# sound_localizer_v1.net
KiCad netlist of a schematic drawn in EAGLE
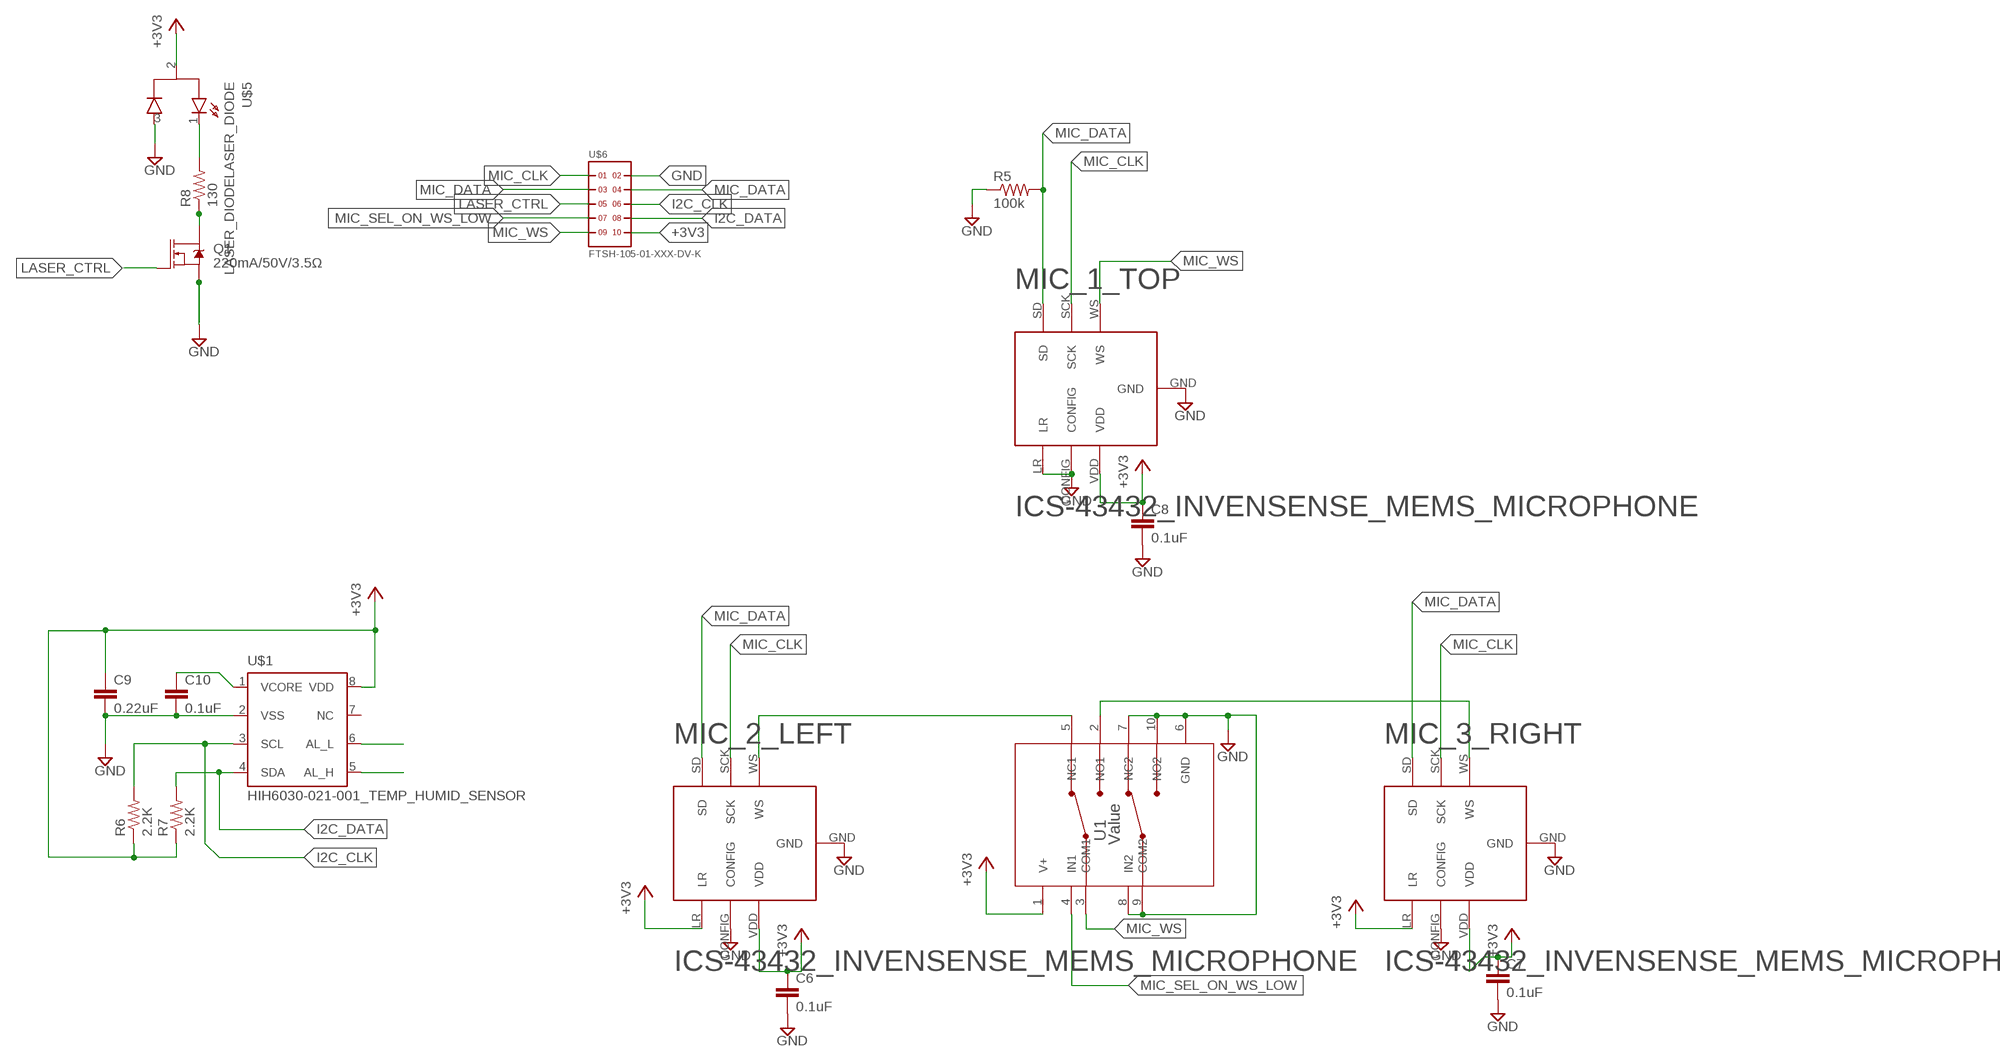
[diagram p0: schematic, sheet 1]

(export (version "E")
  (design (tool "Eeschema 10.0.6"))
  (components
    (comp (ref "C6")
      (value "0.1uF")
      (footprint "eagle-import:C0805K")
      (libsource (lib "eagle-import") (part "C-EUC0805K"))
    )
    (comp (ref "C7")
      (value "0.1uF")
      (footprint "eagle-import:C0805K")
      (libsource (lib "eagle-import") (part "C-EUC0805K"))
    )
    (comp (ref "C8")
      (value "0.1uF")
      (footprint "eagle-import:C0805K")
      (libsource (lib "eagle-import") (part "C-EUC0805K"))
    )
    (comp (ref "C9")
      (value "0.22uF")
      (footprint "eagle-import:C0805K")
      (libsource (lib "eagle-import") (part "C-EUC0805K"))
    )
    (comp (ref "C10")
      (value "0.1uF")
      (footprint "eagle-import:C0805K")
      (libsource (lib "eagle-import") (part "C-EUC0805K"))
    )
    (comp (ref "MIC_1_TOP")
      (value "ICS-43432_INVENSENSE_MEMS_MICROPHONE")
      (footprint "eagle-import:MEMS_MIC")
      (libsource (lib "eagle-import") (part "ICS-43432_INVENSENSE_MEMS_MICROPHONE"))
    )
    (comp (ref "MIC_2_LEFT")
      (value "ICS-43432_INVENSENSE_MEMS_MICROPHONE")
      (footprint "eagle-import:MEMS_MIC")
      (libsource (lib "eagle-import") (part "ICS-43432_INVENSENSE_MEMS_MICROPHONE"))
    )
    (comp (ref "MIC_3_RIGHT")
      (value "ICS-43432_INVENSENSE_MEMS_MICROPHONE")
      (footprint "eagle-import:MEMS_MIC")
      (libsource (lib "eagle-import") (part "ICS-43432_INVENSENSE_MEMS_MICROPHONE"))
    )
    (comp (ref "Q1")
      (value "220mA/50V/3.5Ω")
      (footprint "eagle-import:SOT23-3")
      (libsource (lib "eagle-import") (part "MOSFET-NCH-BSS138"))
    )
    (comp (ref "R5")
      (value "100k")
      (footprint "eagle-import:M0805")
      (libsource (lib "eagle-import") (part "R-US_M0805"))
    )
    (comp (ref "R6")
      (value "2.2K")
      (footprint "eagle-import:M0805")
      (libsource (lib "eagle-import") (part "R-US_M0805"))
    )
    (comp (ref "R7")
      (value "2.2K")
      (footprint "eagle-import:M0805")
      (libsource (lib "eagle-import") (part "R-US_M0805"))
    )
    (comp (ref "R8")
      (value "130")
      (footprint "eagle-import:M0805")
      (libsource (lib "eagle-import") (part "R-US_M0805"))
    )
    (comp (ref "U$1")
      (value "HIH6030-021-001_TEMP_HUMID_SENSOR")
      (footprint "eagle-import:SOIC8")
      (libsource (lib "eagle-import") (part "HIH6030-021-001_TEMP_HUMID_SENSOR"))
    )
    (comp (ref "U$5")
      (value "LASER_DIODELASER_DIODE")
      (footprint "eagle-import:TO46-LX")
      (libsource (lib "eagle-import") (part "LASER_DIODELASER_DIODE"))
    )
    (comp (ref "U$6")
      (value "FTSH-105-01-XXX-DV-K")
      (footprint "eagle-import:FTSH-105-01-XXX-DV-K")
      (libsource (lib "eagle-import") (part "FTSH-105-01-XXX-DV-K"))
    )
    (comp (ref "U1")
      (value "Value")
      (footprint "eagle-import:DGS0010A_N")
      (fields (field (name "MANUFACTURER") "Texas Instruments") (field (name "PARTNUMBER") "TS3A24159DGSR"))
      (libsource (lib "eagle-import") (part "TS3A24159DGSR"))
    )
  )
  (nets
    (net (code "1") (name "+3V3") (class "Default")
      (node (ref "C6") (pin "1") (pinfunction "1_1") (pintype "passive"))
      (node (ref "C7") (pin "1") (pinfunction "1_1") (pintype "passive"))
      (node (ref "C8") (pin "1") (pinfunction "1_1") (pintype "passive"))
      (node (ref "C9") (pin "1") (pinfunction "1_1") (pintype "passive"))
      (node (ref "MIC_1_TOP") (pin "VDD") (pinfunction "VDD_VDD") (pintype "power_in"))
      (node (ref "MIC_2_LEFT") (pin "LR") (pinfunction "LR_LR") (pintype "bidirectional"))
      (node (ref "MIC_2_LEFT") (pin "VDD") (pinfunction "VDD_VDD") (pintype "power_in"))
      (node (ref "MIC_3_RIGHT") (pin "LR") (pinfunction "LR_LR") (pintype "bidirectional"))
      (node (ref "MIC_3_RIGHT") (pin "VDD") (pinfunction "VDD_VDD") (pintype "power_in"))
      (node (ref "R6") (pin "1") (pinfunction "1_1") (pintype "passive"))
      (node (ref "R7") (pin "1") (pinfunction "1_1") (pintype "passive"))
      (node (ref "U$1") (pin "8") (pinfunction "VDD_8") (pintype "power_in"))
      (node (ref "U$5") (pin "2") (pinfunction "2_2") (pintype "bidirectional"))
      (node (ref "U$6") (pin "10") (pinfunction "10_10") (pintype "bidirectional"))
      (node (ref "U1") (pin "1") (pinfunction "V+_1") (pintype "power_in"))
    )
    (net (code "2") (name "/P$1") (class "Default")
      (node (ref "U$5") (pin "3") (pinfunction "P$1_3") (pintype "power_in"))
    )
    (net (code "3") (name "GND") (class "Default")
      (node (ref "C10") (pin "2") (pinfunction "2_2") (pintype "passive"))
      (node (ref "C6") (pin "2") (pinfunction "2_2") (pintype "passive"))
      (node (ref "C7") (pin "2") (pinfunction "2_2") (pintype "passive"))
      (node (ref "C8") (pin "2") (pinfunction "2_2") (pintype "passive"))
      (node (ref "C9") (pin "2") (pinfunction "2_2") (pintype "passive"))
      (node (ref "MIC_1_TOP") (pin "CONFIG") (pinfunction "CONFIG_CONFIG") (pintype "bidirectional"))
      (node (ref "MIC_1_TOP") (pin "GND") (pinfunction "GND_GND") (pintype "power_in"))
      (node (ref "MIC_1_TOP") (pin "LR") (pinfunction "LR_LR") (pintype "bidirectional"))
      (node (ref "MIC_2_LEFT") (pin "CONFIG") (pinfunction "CONFIG_CONFIG") (pintype "bidirectional"))
      (node (ref "MIC_2_LEFT") (pin "GND") (pinfunction "GND_GND") (pintype "power_in"))
      (node (ref "MIC_3_RIGHT") (pin "CONFIG") (pinfunction "CONFIG_CONFIG") (pintype "bidirectional"))
      (node (ref "MIC_3_RIGHT") (pin "GND") (pinfunction "GND_GND") (pintype "power_in"))
      (node (ref "Q1") (pin "2") (pinfunction "S_2") (pintype "bidirectional"))
      (node (ref "R5") (pin "1") (pinfunction "1_1") (pintype "passive"))
      (node (ref "U$1") (pin "2") (pinfunction "VSS_2") (pintype "power_in"))
      (node (ref "U$6") (pin "2") (pinfunction "2_2") (pintype "bidirectional"))
      (node (ref "U1") (pin "10") (pinfunction "NO2_10") (pintype "passive"))
      (node (ref "U1") (pin "6") (pinfunction "GND_6") (pintype "power_in"))
      (node (ref "U1") (pin "7") (pinfunction "NC2_7") (pintype "passive"))
      (node (ref "U1") (pin "8") (pinfunction "IN2_8") (pintype "input"))
      (node (ref "U1") (pin "9") (pinfunction "COM2_9") (pintype "passive"))
    )
    (net (code "4") (name "I2C_CLK") (class "Default")
      (node (ref "R6") (pin "2") (pinfunction "2_2") (pintype "passive"))
      (node (ref "U$1") (pin "3") (pinfunction "SCL_3") (pintype "input"))
      (node (ref "U$6") (pin "6") (pinfunction "6_6") (pintype "bidirectional"))
    )
    (net (code "5") (name "I2C_DATA") (class "Default")
      (node (ref "R7") (pin "2") (pinfunction "2_2") (pintype "passive"))
      (node (ref "U$1") (pin "4") (pinfunction "SDA_4") (pintype "bidirectional"))
      (node (ref "U$6") (pin "8") (pinfunction "8_8") (pintype "bidirectional"))
    )
    (net (code "6") (name "LASER_CTRL") (class "Default")
      (node (ref "Q1") (pin "1") (pinfunction "G_1") (pintype "bidirectional"))
      (node (ref "U$6") (pin "5") (pinfunction "5_5") (pintype "bidirectional"))
    )
    (net (code "7") (name "MIC_CLK") (class "Default")
      (node (ref "MIC_1_TOP") (pin "SCK") (pinfunction "SCK_SCK") (pintype "input"))
      (node (ref "MIC_2_LEFT") (pin "SCK") (pinfunction "SCK_SCK") (pintype "input"))
      (node (ref "MIC_3_RIGHT") (pin "SCK") (pinfunction "SCK_SCK") (pintype "input"))
      (node (ref "U$6") (pin "1") (pinfunction "1_1") (pintype "bidirectional"))
    )
    (net (code "8") (name "MIC_DATA") (class "Default")
      (node (ref "MIC_1_TOP") (pin "SD") (pinfunction "SD_SD") (pintype "bidirectional"))
      (node (ref "MIC_2_LEFT") (pin "SD") (pinfunction "SD_SD") (pintype "bidirectional"))
      (node (ref "MIC_3_RIGHT") (pin "SD") (pinfunction "SD_SD") (pintype "bidirectional"))
      (node (ref "R5") (pin "2") (pinfunction "2_2") (pintype "passive"))
      (node (ref "U$6") (pin "3") (pinfunction "3_3") (pintype "bidirectional"))
      (node (ref "U$6") (pin "4") (pinfunction "4_4") (pintype "bidirectional"))
    )
    (net (code "9") (name "MIC_SEL_ON_WS_LOW") (class "Default")
      (node (ref "U$6") (pin "7") (pinfunction "7_7") (pintype "bidirectional"))
      (node (ref "U1") (pin "4") (pinfunction "IN1_4") (pintype "input"))
    )
    (net (code "10") (name "MIC_WS") (class "Default")
      (node (ref "MIC_1_TOP") (pin "WS") (pinfunction "WS_WS") (pintype "bidirectional"))
      (node (ref "U$6") (pin "9") (pinfunction "9_9") (pintype "bidirectional"))
      (node (ref "U1") (pin "3") (pinfunction "COM1_3") (pintype "passive"))
    )
    (net (code "11") (name "Net-(Q1-D)") (class "Default")
      (node (ref "Q1") (pin "3") (pinfunction "D_3") (pintype "bidirectional"))
      (node (ref "R8") (pin "1") (pinfunction "1_1") (pintype "passive"))
    )
    (net (code "12") (name "Net-(R8-Pad2)") (class "Default")
      (node (ref "R8") (pin "2") (pinfunction "2_2") (pintype "passive"))
      (node (ref "U$5") (pin "1") (pinfunction "1_1") (pintype "passive"))
    )
    (net (code "13") (name "Net-(U$1-VCORE)") (class "Default")
      (node (ref "C10") (pin "1") (pinfunction "1_1") (pintype "passive"))
      (node (ref "U$1") (pin "1") (pinfunction "VCORE_1") (pintype "input"))
    )
    (net (code "14") (name "Net-(U1-NC1)") (class "Default")
      (node (ref "MIC_2_LEFT") (pin "WS") (pinfunction "WS_WS") (pintype "bidirectional"))
      (node (ref "U1") (pin "5") (pinfunction "NC1_5") (pintype "passive"))
    )
    (net (code "15") (name "Net-(U1-NO1)") (class "Default")
      (node (ref "MIC_3_RIGHT") (pin "WS") (pinfunction "WS_WS") (pintype "bidirectional"))
      (node (ref "U1") (pin "2") (pinfunction "NO1_2") (pintype "passive"))
    )
    (net (code "16") (name "unconnected-(U$1-AL_H-Pad5)") (class "Default")
      (node (ref "U$1") (pin "5") (pinfunction "AL_H_5") (pintype "output"))
    )
    (net (code "17") (name "unconnected-(U$1-AL_L-Pad6)") (class "Default")
      (node (ref "U$1") (pin "6") (pinfunction "AL_L_6") (pintype "output"))
    )
    (net (code "18") (name "unconnected-(U$1-NC-Pad7)") (class "Default")
      (node (ref "U$1") (pin "7") (pinfunction "NC_7") (pintype "no_connect"))
    )
  )
)
